# Patch_panel_module_-_De-normalled.net
KiCad netlist of a schematic drawn in EAGLE
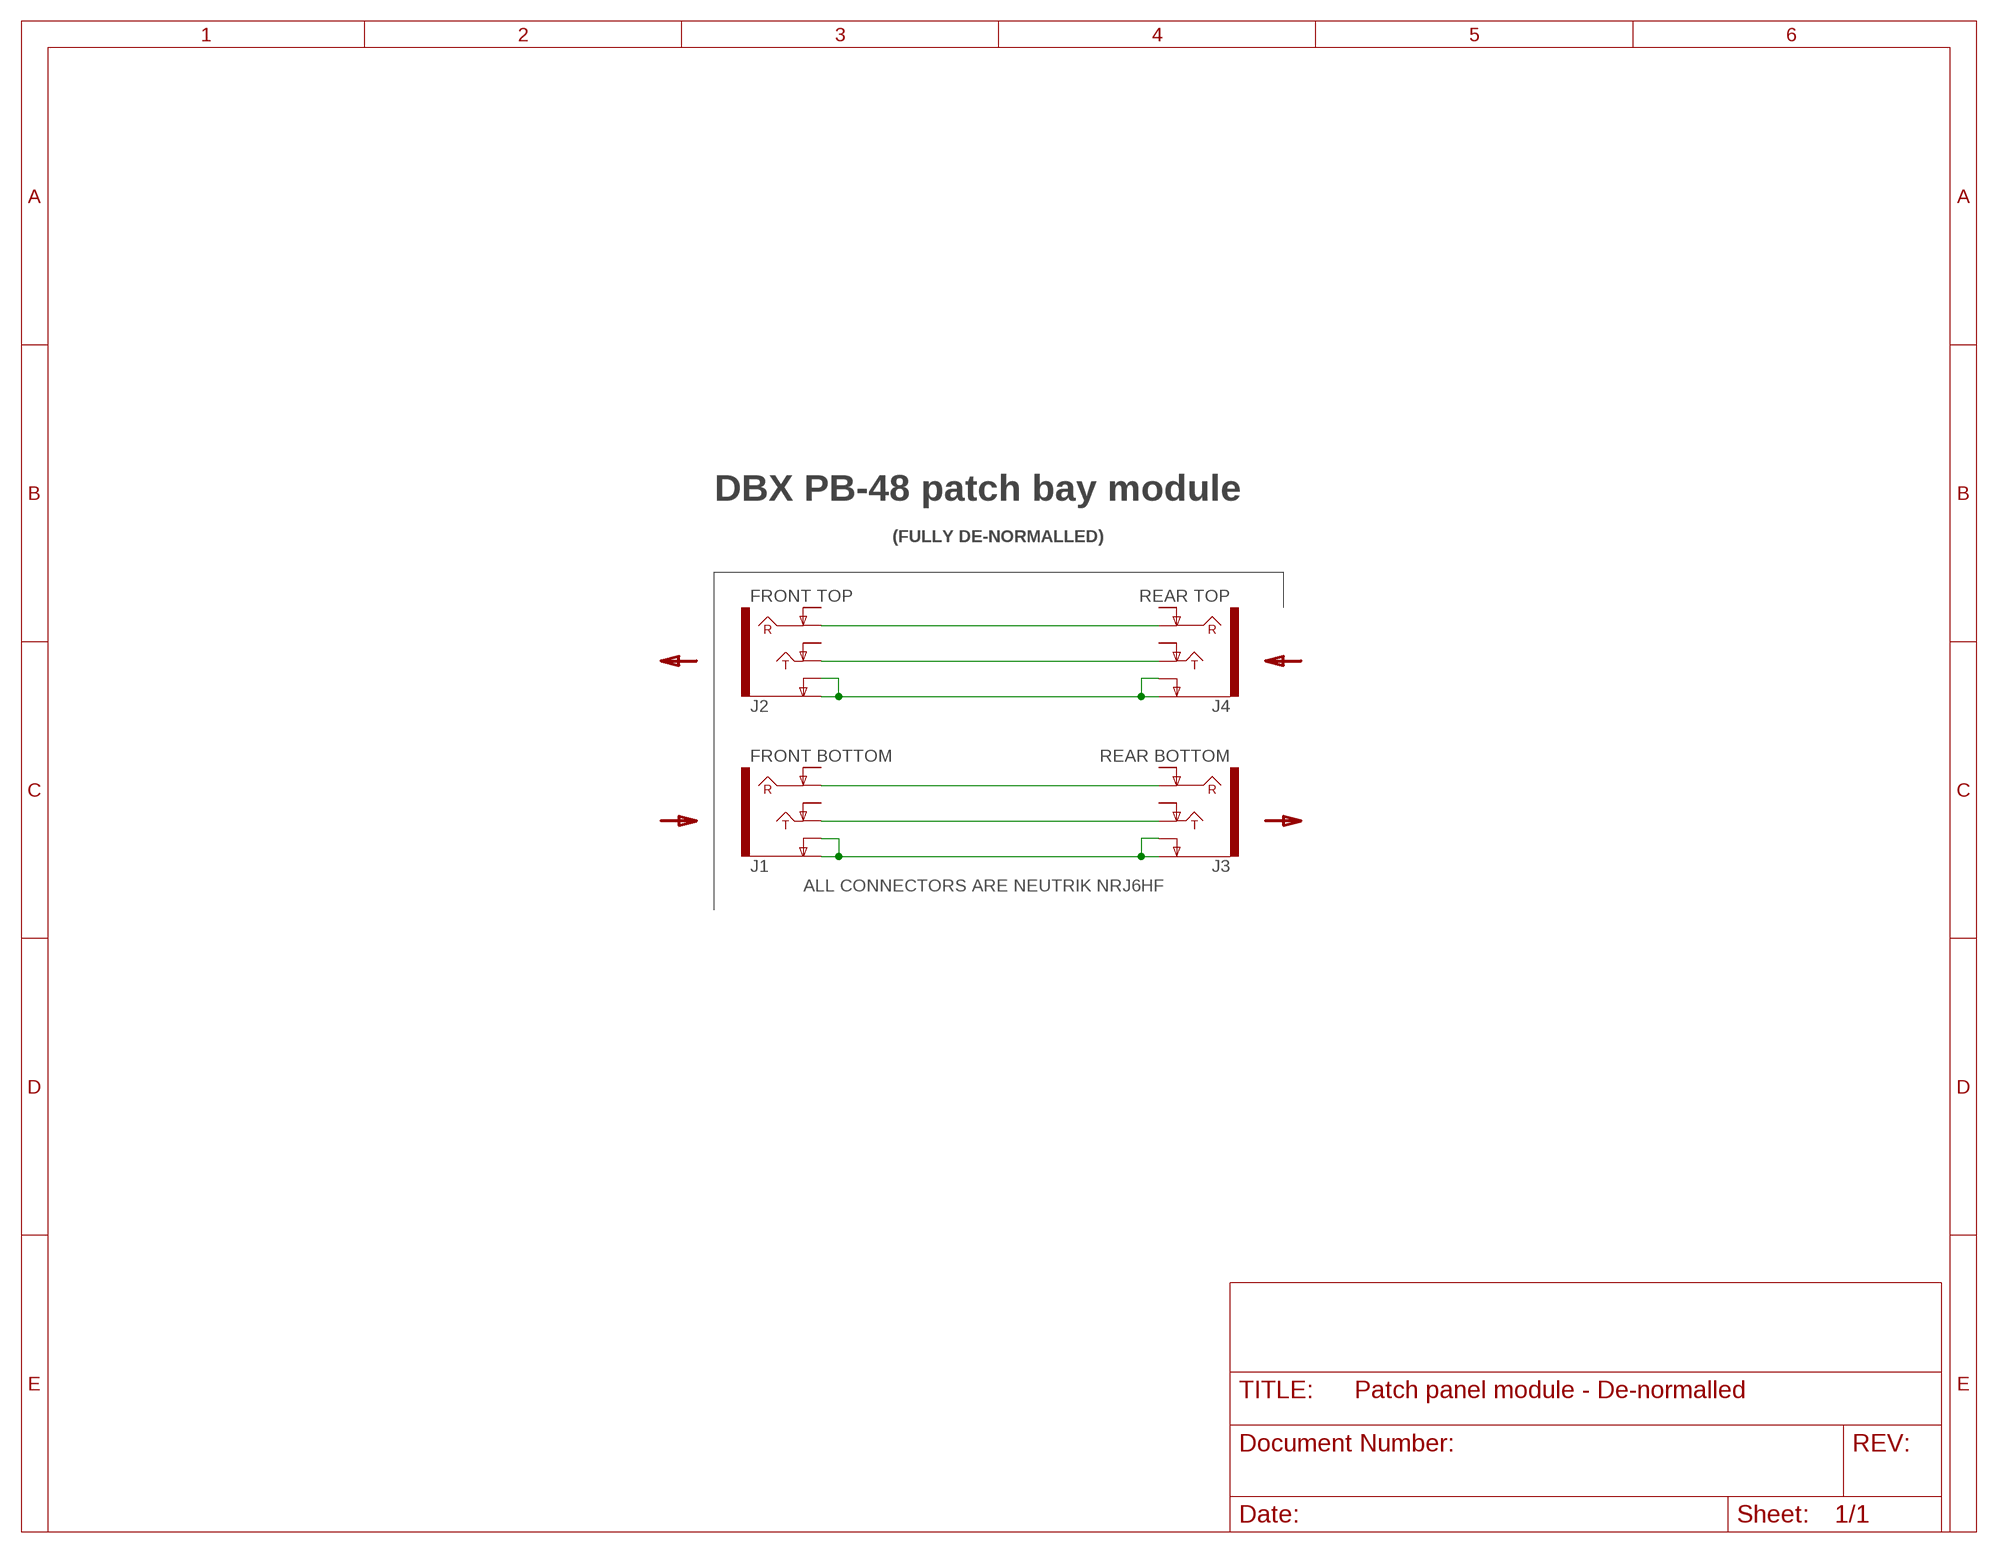
[diagram p0: schematic, sheet 1]

(export (version "E")
  (design (tool "Eeschema 10.0.6"))
  (components
    (comp (ref "J1")
      (value "FRONT BOTTOM")
      (footprint "eagle-import:NEUTRIK-NRJ6HF")
      (libsource (lib "eagle-import") (part "AUDIO_JACK_TRS_0.25{dblquote}_PTH_RA-NRJ6HM"))
    )
    (comp (ref "J2")
      (value "FRONT TOP")
      (footprint "eagle-import:NEUTRIK-NRJ6HF")
      (libsource (lib "eagle-import") (part "AUDIO_JACK_TRS_0.25{dblquote}_PTH_RA-NRJ6HM"))
    )
    (comp (ref "J3")
      (value "REAR BOTTOM")
      (footprint "eagle-import:NEUTRIK-NRJ6HF")
      (libsource (lib "eagle-import") (part "AUDIO_JACK_TRS_0.25{dblquote}_PTH_RA-NRJ6HM"))
    )
    (comp (ref "J4")
      (value "REAR TOP")
      (footprint "eagle-import:NEUTRIK-NRJ6HF")
      (libsource (lib "eagle-import") (part "AUDIO_JACK_TRS_0.25{dblquote}_PTH_RA-NRJ6HM"))
    )
  )
  (nets
    (net (code "1") (name "Net-(J1-EARTH)") (class "Default")
      (node (ref "J1") (pin "S") (pinfunction "EARTH_S") (pintype "bidirectional"))
      (node (ref "J1") (pin "SN") (pinfunction "EARTH-NORM_SN") (pintype "bidirectional"))
      (node (ref "J3") (pin "S") (pinfunction "EARTH_S") (pintype "bidirectional"))
      (node (ref "J3") (pin "SN") (pinfunction "EARTH-NORM_SN") (pintype "bidirectional"))
    )
    (net (code "2") (name "Net-(J1-RING)") (class "Default")
      (node (ref "J1") (pin "R") (pinfunction "RING_R") (pintype "bidirectional"))
      (node (ref "J3") (pin "R") (pinfunction "RING_R") (pintype "bidirectional"))
    )
    (net (code "3") (name "Net-(J1-TIP)") (class "Default")
      (node (ref "J1") (pin "T") (pinfunction "TIP_T") (pintype "bidirectional"))
      (node (ref "J3") (pin "T") (pinfunction "TIP_T") (pintype "bidirectional"))
    )
    (net (code "4") (name "Net-(J2-EARTH)") (class "Default")
      (node (ref "J2") (pin "S") (pinfunction "EARTH_S") (pintype "bidirectional"))
      (node (ref "J2") (pin "SN") (pinfunction "EARTH-NORM_SN") (pintype "bidirectional"))
      (node (ref "J4") (pin "S") (pinfunction "EARTH_S") (pintype "bidirectional"))
      (node (ref "J4") (pin "SN") (pinfunction "EARTH-NORM_SN") (pintype "bidirectional"))
    )
    (net (code "5") (name "Net-(J2-RING)") (class "Default")
      (node (ref "J2") (pin "R") (pinfunction "RING_R") (pintype "bidirectional"))
      (node (ref "J4") (pin "R") (pinfunction "RING_R") (pintype "bidirectional"))
    )
    (net (code "6") (name "Net-(J2-TIP)") (class "Default")
      (node (ref "J2") (pin "T") (pinfunction "TIP_T") (pintype "bidirectional"))
      (node (ref "J4") (pin "T") (pinfunction "TIP_T") (pintype "bidirectional"))
    )
    (net (code "7") (name "unconnected-(J1-RING-NORM-PadRN)") (class "Default")
      (node (ref "J1") (pin "RN") (pinfunction "RING-NORM_RN") (pintype "bidirectional"))
    )
    (net (code "8") (name "unconnected-(J1-TIP-NORM-PadTN)") (class "Default")
      (node (ref "J1") (pin "TN") (pinfunction "TIP-NORM_TN") (pintype "bidirectional"))
    )
    (net (code "9") (name "unconnected-(J2-RING-NORM-PadRN)") (class "Default")
      (node (ref "J2") (pin "RN") (pinfunction "RING-NORM_RN") (pintype "bidirectional"))
    )
    (net (code "10") (name "unconnected-(J2-TIP-NORM-PadTN)") (class "Default")
      (node (ref "J2") (pin "TN") (pinfunction "TIP-NORM_TN") (pintype "bidirectional"))
    )
    (net (code "11") (name "unconnected-(J3-RING-NORM-PadRN)") (class "Default")
      (node (ref "J3") (pin "RN") (pinfunction "RING-NORM_RN") (pintype "bidirectional"))
    )
    (net (code "12") (name "unconnected-(J3-TIP-NORM-PadTN)") (class "Default")
      (node (ref "J3") (pin "TN") (pinfunction "TIP-NORM_TN") (pintype "bidirectional"))
    )
    (net (code "13") (name "unconnected-(J4-RING-NORM-PadRN)") (class "Default")
      (node (ref "J4") (pin "RN") (pinfunction "RING-NORM_RN") (pintype "bidirectional"))
    )
    (net (code "14") (name "unconnected-(J4-TIP-NORM-PadTN)") (class "Default")
      (node (ref "J4") (pin "TN") (pinfunction "TIP-NORM_TN") (pintype "bidirectional"))
    )
  )
)
